# AC.net
KiCad netlist of a schematic drawn in Altium Designer
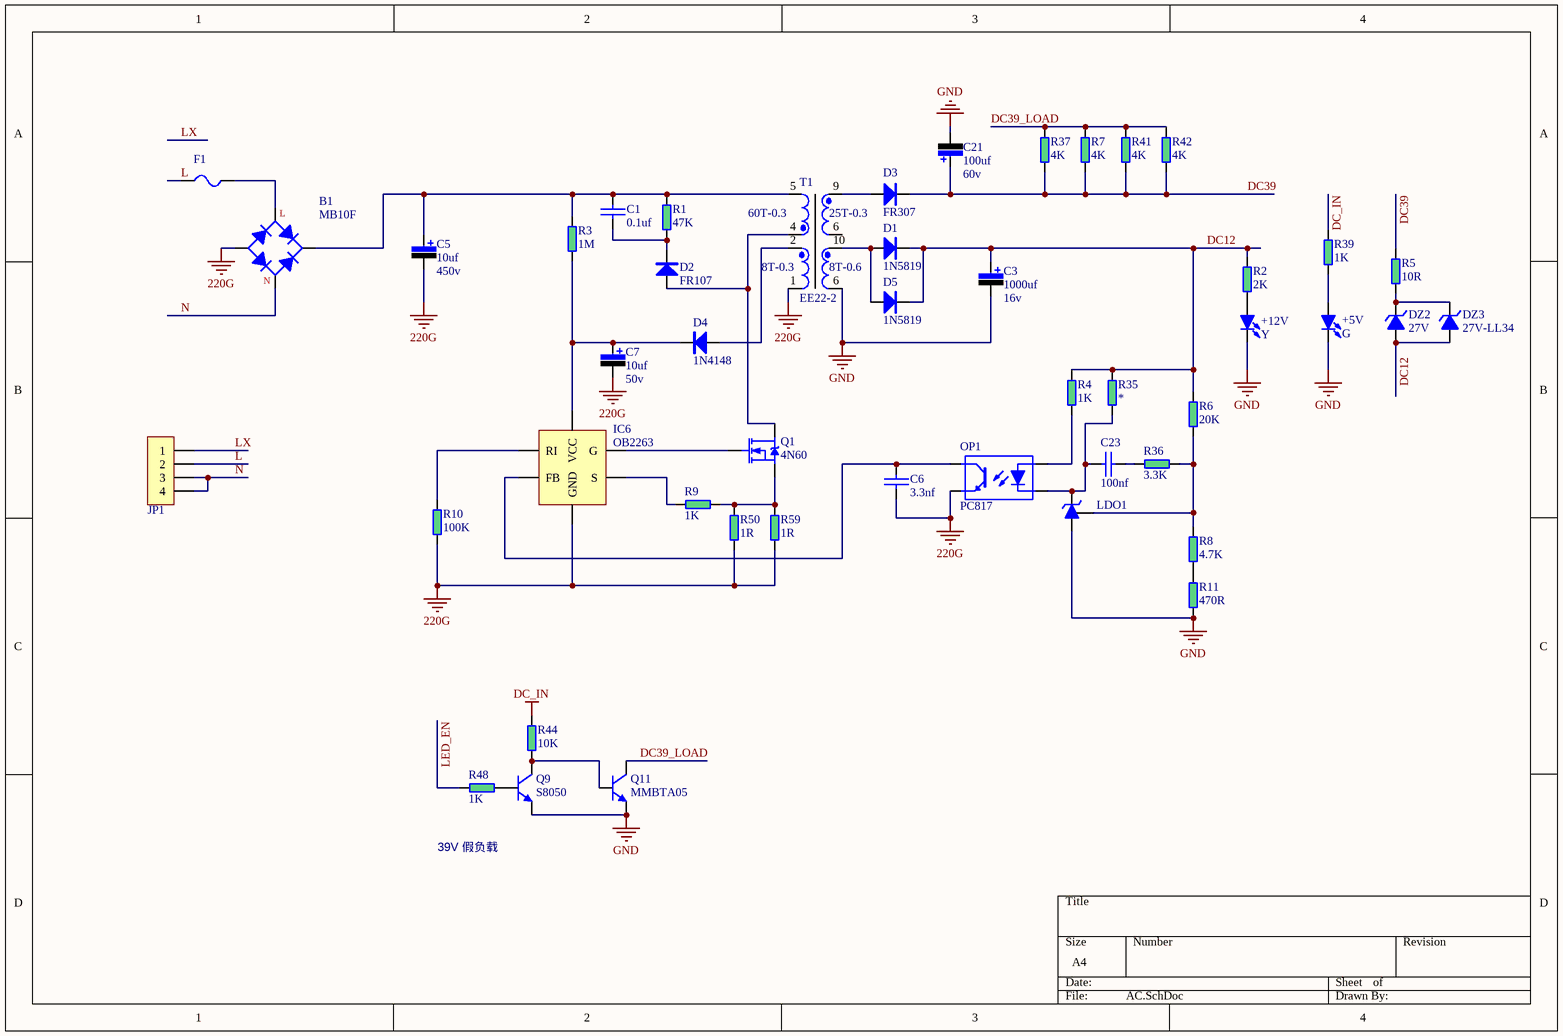
[diagram p0: AC.SchDoc]

(export (version "E")
  (design (tool "Eeschema 10.0.6"))
  (components
    (comp (ref "+5V")
      (value "G")
      (footprint "LED 0603B")
      (description "LED")
      (libsource (lib "电子元件") (part "15.Diode - LED"))
    )
    (comp (ref "+12V")
      (value "Y")
      (footprint "LED 0603B")
      (description "LED")
      (libsource (lib "电子元件") (part "15.Diode - LED"))
    )
    (comp (ref "B1")
      (value "MB10F")
      (footprint "D MBF")
      (description "整流桥")
      (libsource (lib "电子元件") (part "14.Diode - Rectifier"))
    )
    (comp (ref "C1")
      (value "0.1uf")
      (footprint "CY 5*7")
      (description "电容")
      (fields (field (name "Comment") "04.Cap"))
      (libsource (lib "电子元件") (part "04.Cap"))
    )
    (comp (ref "C3")
      (value "16v")
      (footprint "CAP 16v1000uf（8*11）")
      (description "电解电容")
      (fields (field (name "ALTIUM_VALUE") "1000uf") (field (name "Comment") "05.Cap-EC"))
      (libsource (lib "电子元件") (part "05.Cap-EC"))
    )
    (comp (ref "C5")
      (value "450v")
      (footprint "CAP 450v10uf（10*16）")
      (description "电解电容")
      (fields (field (name "ALTIUM_VALUE") "10uf") (field (name "Comment") "05.Cap-EC"))
      (libsource (lib "电子元件") (part "05.Cap-EC"))
    )
    (comp (ref "C6")
      (value "3.3nf")
      (footprint "C 0603")
      (description "电容")
      (fields (field (name "Comment") "04.Cap"))
      (libsource (lib "电子元件") (part "04.Cap"))
    )
    (comp (ref "C7")
      (value "50v")
      (footprint "CAP 50v10uf（5*8）")
      (description "电解电容")
      (fields (field (name "ALTIUM_VALUE") "10uf") (field (name "Comment") "05.Cap-EC"))
      (libsource (lib "电子元件") (part "05.Cap-EC"))
    )
    (comp (ref "C21")
      (value "60v")
      (footprint "CAP 63V100uf（8*11）")
      (description "电解电容")
      (fields (field (name "ALTIUM_VALUE") "100uf") (field (name "Comment") "05.Cap-EC"))
      (libsource (lib "") (part "05.Cap-EC_1"))
    )
    (comp (ref "C23")
      (value "100nf")
      (footprint "C 0603")
      (description "电容")
      (fields (field (name "Comment") "04.Cap"))
      (libsource (lib "电子元件") (part "04.Cap"))
    )
    (comp (ref "D1")
      (value "1N5819")
      (footprint "DO-41V")
      (description "二极管")
      (libsource (lib "电子元件") (part "12.Diode"))
    )
    (comp (ref "D2")
      (value "FR107")
      (footprint "DO-41")
      (description "二极管")
      (libsource (lib "电子元件") (part "12.Diode"))
    )
    (comp (ref "D3")
      (value "FR307")
      (footprint "DO-201ADV")
      (description "二极管")
      (libsource (lib "电子元件") (part "12.Diode"))
    )
    (comp (ref "D4")
      (value "1N4148")
      (footprint "D 1N4148-LL34")
      (description "二极管")
      (libsource (lib "电子元件") (part "12.Diode"))
    )
    (comp (ref "D5")
      (value "1N5819")
      (footprint "DO-41V")
      (description "二极管")
      (libsource (lib "电子元件") (part "12.Diode"))
    )
    (comp (ref "DZ2")
      (value "27V")
      (footprint "D 1N4750/1W/27V/LL41")
      (description "稳压管")
      (libsource (lib "电子元件") (part "13.Diode - Zen"))
    )
    (comp (ref "DZ3")
      (value "27V-LL34")
      (footprint "D ZMM4V7-LL34")
      (description "稳压管")
      (libsource (lib "电子元件") (part "13.Diode - Zen"))
    )
    (comp (ref "F1")
      (value "11.Fuse")
      (footprint "FU 3x10")
      (description "保险丝")
      (libsource (lib "电子元件") (part "11.Fuse"))
    )
    (comp (ref "IC6") (value "OB2263") (footprint "SOT23-6L") (libsource (lib "集成IC") (part "OB2263")))
    (comp (ref "JP1") (value "Pin04") (footprint "KF7620-4P") (libsource (lib "接插件") (part "Pin04")))
    (comp (ref "LDO1")
      (value "TL431")
      (footprint "P TL431-SOT23")
      (description "电压基准（out=Ref*(1+R1/R2)）")
      (libsource (lib "集成IC") (part "TL431"))
    )
    (comp (ref "OP1")
      (value "PC817")
      (footprint "OP PC817-SMD")
      (description "光耦")
      (libsource (lib "电子元件") (part "17.Optocoupler"))
    )
    (comp (ref "Q1")
      (value "4N60")
      (footprint "FET-AOD4N60/600V/4A-TO252")
      (description "MOS管 NPN")
      (libsource (lib "电子元件") (part "09.FET(N)"))
    )
    (comp (ref "Q9")
      (value "S8050")
      (footprint "BJT-S8050/40V/1.5A-SOT23")
      (description "三极管 NPN")
      (libsource (lib "电子元件") (part "07.BJT(N)"))
    )
    (comp (ref "Q11")
      (value "MMBTA05")
      (footprint "BJT-MMBTA05/60V/0.5A-SOT23")
      (description "三极管 NPN")
      (libsource (lib "电子元件") (part "07.BJT(N)"))
    )
    (comp (ref "R1")
      (value "47K")
      (footprint "RS 1/2W-V4")
      (description "电阻")
      (libsource (lib "") (part "01.Res_2"))
    )
    (comp (ref "R2")
      (value "2K")
      (footprint "R 0603")
      (description "电阻")
      (libsource (lib "") (part "01.Res_1"))
    )
    (comp (ref "R3")
      (value "1M")
      (footprint "RS 1/4W-V3")
      (description "电阻")
      (libsource (lib "") (part "01.Res_2"))
    )
    (comp (ref "R4")
      (value "1K")
      (footprint "R 0603")
      (description "电阻")
      (libsource (lib "") (part "01.Res_1"))
    )
    (comp (ref "R5")
      (value "10R")
      (footprint "R 1206")
      (description "电阻")
      (libsource (lib "") (part "01.Res_2"))
    )
    (comp (ref "R6")
      (value "20K")
      (footprint "R 0603")
      (description "电阻")
      (libsource (lib "") (part "01.Res_1"))
    )
    (comp (ref "R7")
      (value "4K")
      (footprint "RS 1W-V5")
      (description "电阻")
      (libsource (lib "") (part "01.Res_2"))
    )
    (comp (ref "R8")
      (value "4.7K")
      (footprint "R 0603")
      (description "电阻")
      (libsource (lib "") (part "01.Res_1"))
    )
    (comp (ref "R9")
      (value "1K")
      (footprint "R 0603")
      (description "电阻")
      (libsource (lib "电子元件") (part "01.Res"))
    )
    (comp (ref "R10")
      (value "100K")
      (footprint "R 0603")
      (description "电阻")
      (libsource (lib "") (part "01.Res_1"))
    )
    (comp (ref "R11")
      (value "470R")
      (footprint "R 0603")
      (description "电阻")
      (libsource (lib "") (part "01.Res_1"))
    )
    (comp (ref "R35")
      (value "*")
      (footprint "R 0603")
      (description "电阻")
      (libsource (lib "") (part "01.Res_1"))
    )
    (comp (ref "R36")
      (value "3.3K")
      (footprint "R 0603")
      (description "电阻")
      (libsource (lib "电子元件") (part "01.Res"))
    )
    (comp (ref "R37")
      (value "4K")
      (footprint "RS 1W-V5")
      (description "电阻")
      (libsource (lib "") (part "01.Res_2"))
    )
    (comp (ref "R39")
      (value "1K")
      (footprint "R 0603")
      (description "电阻")
      (libsource (lib "") (part "01.Res_1"))
    )
    (comp (ref "R41")
      (value "4K")
      (footprint "RS 1W-V5")
      (description "电阻")
      (libsource (lib "") (part "01.Res_2"))
    )
    (comp (ref "R42")
      (value "4K")
      (footprint "RS 1W-V5")
      (description "电阻")
      (libsource (lib "") (part "01.Res_2"))
    )
    (comp (ref "R44")
      (value "10K")
      (footprint "R 0603")
      (description "电阻")
      (libsource (lib "") (part "01.Res_1"))
    )
    (comp (ref "R48")
      (value "1K")
      (footprint "R 0603")
      (description "电阻")
      (libsource (lib "电子元件") (part "01.Res"))
    )
    (comp (ref "R50")
      (value "1R")
      (footprint "R 1206")
      (description "电阻")
      (libsource (lib "") (part "01.Res_1"))
    )
    (comp (ref "R59")
      (value "1R")
      (footprint "R 1206")
      (description "电阻")
      (libsource (lib "") (part "01.Res_1"))
    )
    (comp (ref "T1") (value "EE22-2") (footprint "EE22") (libsource (lib "高频变压器") (part "EE22-2")))
  )
  (nets
    (net (code "1") (name "/DC12") (class "Default")
      (node (ref "C3") (pin "1") (pinfunction "1_1") (pintype "passive"))
      (node (ref "D1") (pin "K") (pinfunction "K_K") (pintype "passive"))
      (node (ref "D5") (pin "K") (pinfunction "K_K") (pintype "passive"))
      (node (ref "DZ2") (pin "A") (pinfunction "A_A") (pintype "passive"))
      (node (ref "DZ3") (pin "A") (pinfunction "A_A") (pintype "passive"))
      (node (ref "R2") (pin "2") (pinfunction "2_2") (pintype "passive"))
      (node (ref "R35") (pin "2") (pinfunction "2_2") (pintype "passive"))
      (node (ref "R4") (pin "2") (pinfunction "2_2") (pintype "passive"))
      (node (ref "R6") (pin "2") (pinfunction "2_2") (pintype "passive"))
    )
    (net (code "2") (name "/DC39") (class "Default")
      (node (ref "C21") (pin "1") (pinfunction "1_1") (pintype "passive"))
      (node (ref "D3") (pin "K") (pinfunction "K_K") (pintype "passive"))
      (node (ref "R37") (pin "2") (pinfunction "2_2") (pintype "passive"))
      (node (ref "R41") (pin "2") (pinfunction "2_2") (pintype "passive"))
      (node (ref "R42") (pin "2") (pinfunction "2_2") (pintype "passive"))
      (node (ref "R5") (pin "1") (pinfunction "1_1") (pintype "passive"))
      (node (ref "R7") (pin "2") (pinfunction "2_2") (pintype "passive"))
    )
    (net (code "3") (name "/DC39_LOAD") (class "Default")
      (node (ref "Q11") (pin "C") (pinfunction "C_C") (pintype "passive"))
      (node (ref "R37") (pin "1") (pinfunction "1_1") (pintype "passive"))
      (node (ref "R41") (pin "1") (pinfunction "1_1") (pintype "passive"))
      (node (ref "R42") (pin "1") (pinfunction "1_1") (pintype "passive"))
      (node (ref "R7") (pin "1") (pinfunction "1_1") (pintype "passive"))
    )
    (net (code "4") (name "/L") (class "Default")
      (node (ref "F1") (pin "1") (pinfunction "1_1") (pintype "passive"))
      (node (ref "JP1") (pin "2") (pinfunction "2_2") (pintype "passive"))
    )
    (net (code "5") (name "/LED_EN") (class "Default")
      (node (ref "R48") (pin "1") (pinfunction "1_1") (pintype "passive"))
    )
    (net (code "6") (name "/LX") (class "Default")
      (node (ref "JP1") (pin "1") (pinfunction "1_1") (pintype "passive"))
    )
    (net (code "7") (name "/N") (class "Default")
      (node (ref "B1") (pin "AC2") (pinfunction "AC2_AC2") (pintype "passive"))
      (node (ref "JP1") (pin "3") (pinfunction "3_3") (pintype "passive"))
      (node (ref "JP1") (pin "4") (pinfunction "4_4") (pintype "passive"))
    )
    (net (code "8") (name "220G") (class "Default")
      (node (ref "B1") (pin "DC-") (pinfunction "DC-_DC-") (pintype "passive"))
      (node (ref "C5") (pin "2") (pinfunction "2_2") (pintype "passive"))
      (node (ref "C6") (pin "2") (pinfunction "2_2") (pintype "passive"))
      (node (ref "C7") (pin "2") (pinfunction "2_2") (pintype "passive"))
      (node (ref "IC6") (pin "1") (pinfunction "GND_1") (pintype "passive"))
      (node (ref "OP1") (pin "E") (pinfunction "E_E") (pintype "passive"))
      (node (ref "R10") (pin "1") (pinfunction "1_1") (pintype "passive"))
      (node (ref "R50") (pin "1") (pinfunction "1_1") (pintype "passive"))
      (node (ref "R59") (pin "1") (pinfunction "1_1") (pintype "passive"))
      (node (ref "T1") (pin "1") (pinfunction "Sec2-_1") (pintype "passive"))
    )
    (net (code "9") (name "DC_IN") (class "Default")
      (node (ref "R39") (pin "2") (pinfunction "2_2") (pintype "passive"))
      (node (ref "R44") (pin "2") (pinfunction "2_2") (pintype "passive"))
    )
    (net (code "10") (name "GND") (class "Default")
      (node (ref "+12V") (pin "K") (pinfunction "K_K") (pintype "passive"))
      (node (ref "+5V") (pin "K") (pinfunction "K_K") (pintype "passive"))
      (node (ref "C21") (pin "2") (pinfunction "2_2") (pintype "passive"))
      (node (ref "C3") (pin "2") (pinfunction "2_2") (pintype "passive"))
      (node (ref "LDO1") (pin "A") (pinfunction "A_A") (pintype "passive"))
      (node (ref "Q11") (pin "E") (pinfunction "E_E") (pintype "passive"))
      (node (ref "Q9") (pin "E") (pinfunction "E_E") (pintype "passive"))
      (node (ref "R11") (pin "1") (pinfunction "1_1") (pintype "passive"))
      (node (ref "T1") (pin "6") (pinfunction "Pri-_6") (pintype "passive"))
    )
    (net (code "11") (name "Net-(+5V-PadA)") (class "Default")
      (node (ref "+5V") (pin "A") (pinfunction "A_A") (pintype "passive"))
      (node (ref "R39") (pin "1") (pinfunction "1_1") (pintype "passive"))
    )
    (net (code "12") (name "Net-(+12V-PadA)") (class "Default")
      (node (ref "+12V") (pin "A") (pinfunction "A_A") (pintype "passive"))
      (node (ref "R2") (pin "1") (pinfunction "1_1") (pintype "passive"))
    )
    (net (code "13") (name "Net-(B1-PadAC1)") (class "Default")
      (node (ref "B1") (pin "AC1") (pinfunction "AC1_AC1") (pintype "passive"))
      (node (ref "F1") (pin "2") (pinfunction "2_2") (pintype "passive"))
    )
    (net (code "14") (name "Net-(C1-Pad2)") (class "Default")
      (node (ref "C1") (pin "2") (pinfunction "2_2") (pintype "passive"))
      (node (ref "D2") (pin "K") (pinfunction "K_K") (pintype "passive"))
      (node (ref "R1") (pin "2") (pinfunction "2_2") (pintype "passive"))
    )
    (net (code "15") (name "Net-(C23-Pad1)") (class "Default")
      (node (ref "C23") (pin "1") (pinfunction "1_1") (pintype "passive"))
      (node (ref "LDO1") (pin "K") (pinfunction "K_K") (pintype "passive"))
      (node (ref "OP1") (pin "K") (pinfunction "K_K") (pintype "passive"))
      (node (ref "R35") (pin "1") (pinfunction "1_1") (pintype "passive"))
    )
    (net (code "16") (name "Net-(C23-Pad2)") (class "Default")
      (node (ref "C23") (pin "2") (pinfunction "2_2") (pintype "passive"))
      (node (ref "R36") (pin "1") (pinfunction "1_1") (pintype "passive"))
    )
    (net (code "17") (name "Net-(D1-PadA)") (class "Default")
      (node (ref "D1") (pin "A") (pinfunction "A_A") (pintype "passive"))
      (node (ref "D5") (pin "A") (pinfunction "A_A") (pintype "passive"))
      (node (ref "T1") (pin "10") (pinfunction "Pri+_10") (pintype "passive"))
    )
    (net (code "18") (name "Net-(D3-PadA)") (class "Default")
      (node (ref "D3") (pin "A") (pinfunction "A_A") (pintype "passive"))
      (node (ref "T1") (pin "9") (pinfunction "Pri+_9") (pintype "passive"))
    )
    (net (code "19") (name "Net-(DZ2-PadK)") (class "Default")
      (node (ref "DZ2") (pin "K") (pinfunction "K_K") (pintype "passive"))
      (node (ref "DZ3") (pin "K") (pinfunction "K_K") (pintype "passive"))
      (node (ref "R5") (pin "2") (pinfunction "2_2") (pintype "passive"))
    )
    (net (code "20") (name "Net-(IC6-FB)") (class "Default")
      (node (ref "C6") (pin "1") (pinfunction "1_1") (pintype "passive"))
      (node (ref "IC6") (pin "2") (pinfunction "FB_2") (pintype "passive"))
      (node (ref "OP1") (pin "C") (pinfunction "C_C") (pintype "passive"))
    )
    (net (code "21") (name "Net-(IC6-G)") (class "Default")
      (node (ref "IC6") (pin "6") (pinfunction "G_6") (pintype "passive"))
      (node (ref "Q1") (pin "G") (pinfunction "G_G") (pintype "passive"))
    )
    (net (code "22") (name "Net-(IC6-RI)") (class "Default")
      (node (ref "IC6") (pin "3") (pinfunction "RI_3") (pintype "passive"))
      (node (ref "R10") (pin "2") (pinfunction "2_2") (pintype "passive"))
    )
    (net (code "23") (name "Net-(IC6-S)") (class "Default")
      (node (ref "IC6") (pin "4") (pinfunction "S_4") (pintype "passive"))
      (node (ref "R9") (pin "1") (pinfunction "1_1") (pintype "passive"))
    )
    (net (code "24") (name "Net-(IC6-VCC)") (class "Default")
      (node (ref "C7") (pin "1") (pinfunction "1_1") (pintype "passive"))
      (node (ref "D4") (pin "K") (pinfunction "K_K") (pintype "passive"))
      (node (ref "IC6") (pin "5") (pinfunction "VCC_5") (pintype "passive"))
      (node (ref "R3") (pin "2") (pinfunction "2_2") (pintype "passive"))
    )
    (net (code "25") (name "Net-(LDO1-PadR)") (class "Default")
      (node (ref "LDO1") (pin "R") (pinfunction "R_R") (pintype "passive"))
      (node (ref "R36") (pin "2") (pinfunction "2_2") (pintype "passive"))
      (node (ref "R6") (pin "1") (pinfunction "1_1") (pintype "passive"))
      (node (ref "R8") (pin "2") (pinfunction "2_2") (pintype "passive"))
    )
    (net (code "26") (name "Net-(OP1-PadA)") (class "Default")
      (node (ref "OP1") (pin "A") (pinfunction "A_A") (pintype "passive"))
      (node (ref "R4") (pin "1") (pinfunction "1_1") (pintype "passive"))
    )
    (net (code "27") (name "Net-(Q1-PadS)") (class "Default")
      (node (ref "Q1") (pin "S") (pinfunction "S_S") (pintype "passive"))
      (node (ref "R50") (pin "2") (pinfunction "2_2") (pintype "passive"))
      (node (ref "R59") (pin "2") (pinfunction "2_2") (pintype "passive"))
      (node (ref "R9") (pin "2") (pinfunction "2_2") (pintype "passive"))
    )
    (net (code "28") (name "Net-(Q9-PadB)") (class "Default")
      (node (ref "Q9") (pin "B") (pinfunction "B_B") (pintype "passive"))
      (node (ref "R48") (pin "2") (pinfunction "2_2") (pintype "passive"))
    )
    (net (code "29") (name "Net-(Q11-PadB)") (class "Default")
      (node (ref "Q11") (pin "B") (pinfunction "B_B") (pintype "passive"))
      (node (ref "Q9") (pin "C") (pinfunction "C_C") (pintype "passive"))
      (node (ref "R44") (pin "1") (pinfunction "1_1") (pintype "passive"))
    )
    (net (code "30") (name "Net-(R11-Pad2)") (class "Default")
      (node (ref "R11") (pin "2") (pinfunction "2_2") (pintype "passive"))
      (node (ref "R8") (pin "1") (pinfunction "1_1") (pintype "passive"))
    )
    (net (code "31") (name "Net-(T1-Sec1+)") (class "Default")
      (node (ref "B1") (pin "DC+") (pinfunction "DC+_DC+") (pintype "passive"))
      (node (ref "C1") (pin "1") (pinfunction "1_1") (pintype "passive"))
      (node (ref "C5") (pin "1") (pinfunction "1_1") (pintype "passive"))
      (node (ref "R1") (pin "1") (pinfunction "1_1") (pintype "passive"))
      (node (ref "R3") (pin "1") (pinfunction "1_1") (pintype "passive"))
      (node (ref "T1") (pin "5") (pinfunction "Sec1+_5") (pintype "passive"))
    )
    (net (code "32") (name "Net-(T1-Sec1-)") (class "Default")
      (node (ref "D2") (pin "A") (pinfunction "A_A") (pintype "passive"))
      (node (ref "Q1") (pin "D") (pinfunction "D_D") (pintype "passive"))
      (node (ref "T1") (pin "4") (pinfunction "Sec1-_4") (pintype "passive"))
    )
    (net (code "33") (name "Net-(T1-Sec2+)") (class "Default")
      (node (ref "D4") (pin "A") (pinfunction "A_A") (pintype "passive"))
      (node (ref "T1") (pin "2") (pinfunction "Sec2+_2") (pintype "passive"))
    )
    (net (code "34") (name "unconnected-(T1-Pri--Pad6)") (class "Default")
      (node (ref "T1") (pin "6") (pinfunction "Pri-_6") (pintype "passive"))
    )
  )
)
